# shutter.net
KiCad netlist of a schematic drawn in EAGLE
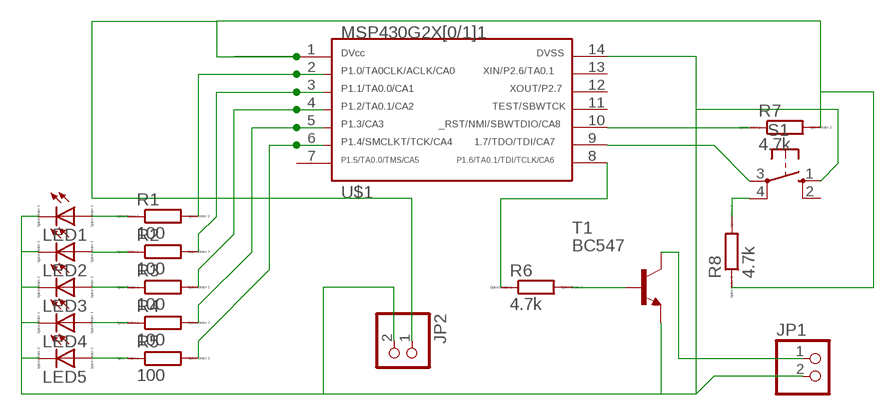
[diagram p0: schematic, sheet 1]

(export (version "E")
  (design (tool "Eeschema 10.0.6"))
  (components
    (comp (ref "JP1")
      (value "PINHD-1X2")
      (footprint "eagle-import:1X02")
      (libsource (lib "eagle-import") (part "PINHD-1X2"))
    )
    (comp (ref "JP2")
      (value "PINHD-1X2")
      (footprint "eagle-import:1X02")
      (libsource (lib "eagle-import") (part "PINHD-1X2"))
    )
    (comp (ref "LED1")
      (value "LED_ESML0603")
      (footprint "eagle-import:LED_SML0603")
      (libsource (lib "eagle-import") (part "LED_ESML0603"))
    )
    (comp (ref "LED2")
      (value "LED_ESML0603")
      (footprint "eagle-import:LED_SML0603")
      (libsource (lib "eagle-import") (part "LED_ESML0603"))
    )
    (comp (ref "LED3")
      (value "LED_ESML0603")
      (footprint "eagle-import:LED_SML0603")
      (libsource (lib "eagle-import") (part "LED_ESML0603"))
    )
    (comp (ref "LED4")
      (value "LED_ESML0603")
      (footprint "eagle-import:LED_SML0603")
      (libsource (lib "eagle-import") (part "LED_ESML0603"))
    )
    (comp (ref "LED5")
      (value "LED_ESML0603")
      (footprint "eagle-import:LED_SML0603")
      (libsource (lib "eagle-import") (part "LED_ESML0603"))
    )
    (comp (ref "R1")
      (value "100")
      (footprint "eagle-import:R0603")
      (libsource (lib "eagle-import") (part "RR0603"))
    )
    (comp (ref "R2")
      (value "100")
      (footprint "eagle-import:R0603")
      (libsource (lib "eagle-import") (part "RR0603"))
    )
    (comp (ref "R3")
      (value "100")
      (footprint "eagle-import:R0603")
      (libsource (lib "eagle-import") (part "RR0603"))
    )
    (comp (ref "R4")
      (value "100")
      (footprint "eagle-import:R0603")
      (libsource (lib "eagle-import") (part "RR0603"))
    )
    (comp (ref "R5")
      (value "100")
      (footprint "eagle-import:R0603")
      (libsource (lib "eagle-import") (part "RR0603"))
    )
    (comp (ref "R6")
      (value "4.7k")
      (footprint "eagle-import:R0603")
      (libsource (lib "eagle-import") (part "RR0603"))
    )
    (comp (ref "R7")
      (value "4.7k")
      (footprint "eagle-import:R0603")
      (libsource (lib "eagle-import") (part "RR0603"))
    )
    (comp (ref "R8")
      (value "4.7k")
      (footprint "eagle-import:R0603")
      (libsource (lib "eagle-import") (part "RR0603"))
    )
    (comp (ref "S1")
      (value "10-XX")
      (footprint "eagle-import:B3F-10XX")
      (fields (field (name "MPN") "B3F-1000"))
      (libsource (lib "eagle-import") (part "10-XX"))
    )
    (comp (ref "T1")
      (value "BC547")
      (footprint "eagle-import:TO92")
      (libsource (lib "eagle-import") (part "BC547"))
    )
    (comp (ref "U$1")
      (value "G2X[0/1]1---PW14")
      (footprint "eagle-import:PW14")
      (libsource (lib "eagle-import") (part "G2X[0/1]1---PW14"))
    )
  )
  (nets
    (net (code "1") (name "Net-(JP2-Pad1)") (class "Default")
      (node (ref "JP2") (pin "1") (pinfunction "1_1") (pintype "passive"))
      (node (ref "R7") (pin "2") (pinfunction "2_2") (pintype "passive"))
      (node (ref "R8") (pin "1") (pinfunction "1_1") (pintype "passive"))
      (node (ref "U$1") (pin "1") (pinfunction "1_1") (pintype "bidirectional"))
    )
    (net (code "2") (name "Net-(LED1-PadA)") (class "Default")
      (node (ref "LED1") (pin "A") (pinfunction "A_A") (pintype "passive"))
      (node (ref "R1") (pin "1") (pinfunction "1_1") (pintype "passive"))
    )
    (net (code "3") (name "Net-(LED2-PadA)") (class "Default")
      (node (ref "LED2") (pin "A") (pinfunction "A_A") (pintype "passive"))
      (node (ref "R2") (pin "1") (pinfunction "1_1") (pintype "passive"))
    )
    (net (code "4") (name "Net-(LED3-PadA)") (class "Default")
      (node (ref "LED3") (pin "A") (pinfunction "A_A") (pintype "passive"))
      (node (ref "R3") (pin "1") (pinfunction "1_1") (pintype "passive"))
    )
    (net (code "5") (name "Net-(LED4-PadA)") (class "Default")
      (node (ref "LED4") (pin "A") (pinfunction "A_A") (pintype "passive"))
      (node (ref "R4") (pin "1") (pinfunction "1_1") (pintype "passive"))
    )
    (net (code "6") (name "Net-(LED5-PadA)") (class "Default")
      (node (ref "LED5") (pin "A") (pinfunction "A_A") (pintype "passive"))
      (node (ref "R5") (pin "1") (pinfunction "1_1") (pintype "passive"))
    )
    (net (code "7") (name "Net-(R1-Pad2)") (class "Default")
      (node (ref "R1") (pin "2") (pinfunction "2_2") (pintype "passive"))
      (node (ref "U$1") (pin "2") (pinfunction "2_2") (pintype "bidirectional"))
    )
    (net (code "8") (name "Net-(R2-Pad2)") (class "Default")
      (node (ref "R2") (pin "2") (pinfunction "2_2") (pintype "passive"))
      (node (ref "U$1") (pin "3") (pinfunction "3_3") (pintype "bidirectional"))
    )
    (net (code "9") (name "Net-(R3-Pad2)") (class "Default")
      (node (ref "R3") (pin "2") (pinfunction "2_2") (pintype "passive"))
      (node (ref "U$1") (pin "4") (pinfunction "4_4") (pintype "bidirectional"))
    )
    (net (code "10") (name "Net-(R4-Pad2)") (class "Default")
      (node (ref "R4") (pin "2") (pinfunction "2_2") (pintype "passive"))
      (node (ref "U$1") (pin "5") (pinfunction "5_5") (pintype "bidirectional"))
    )
    (net (code "11") (name "Net-(R5-Pad2)") (class "Default")
      (node (ref "R5") (pin "2") (pinfunction "2_2") (pintype "passive"))
      (node (ref "U$1") (pin "6") (pinfunction "6_6") (pintype "bidirectional"))
    )
    (net (code "12") (name "Net-(R6-Pad1)") (class "Default")
      (node (ref "R6") (pin "1") (pinfunction "1_1") (pintype "passive"))
      (node (ref "U$1") (pin "8") (pinfunction "8_8") (pintype "bidirectional"))
    )
    (net (code "13") (name "Net-(R7-Pad1)") (class "Default")
      (node (ref "R7") (pin "1") (pinfunction "1_1") (pintype "passive"))
      (node (ref "U$1") (pin "10") (pinfunction "10_10") (pintype "bidirectional"))
    )
    (net (code "14") (name "Net-(S1-P)") (class "Default")
      (node (ref "S1") (pin "3") (pinfunction "P_3") (pintype "passive"))
      (node (ref "U$1") (pin "9") (pinfunction "9_9") (pintype "bidirectional"))
    )
    (net (code "15") (name "Net-(S1-P1)") (class "Default")
      (node (ref "R8") (pin "2") (pinfunction "2_2") (pintype "passive"))
      (node (ref "S1") (pin "4") (pinfunction "P1_4") (pintype "passive"))
    )
    (net (code "16") (name "Net-(S1-S)") (class "Default")
      (node (ref "JP1") (pin "2") (pinfunction "2_2") (pintype "passive"))
      (node (ref "JP2") (pin "2") (pinfunction "2_2") (pintype "passive"))
      (node (ref "LED1") (pin "C") (pinfunction "C_C") (pintype "passive"))
      (node (ref "LED2") (pin "C") (pinfunction "C_C") (pintype "passive"))
      (node (ref "LED3") (pin "C") (pinfunction "C_C") (pintype "passive"))
      (node (ref "LED4") (pin "C") (pinfunction "C_C") (pintype "passive"))
      (node (ref "LED5") (pin "C") (pinfunction "C_C") (pintype "passive"))
      (node (ref "S1") (pin "1") (pinfunction "S_1") (pintype "passive"))
      (node (ref "T1") (pin "1") (pinfunction "E_1") (pintype "passive"))
      (node (ref "U$1") (pin "14") (pinfunction "14_14") (pintype "bidirectional"))
    )
    (net (code "17") (name "Net-(T1-B)") (class "Default")
      (node (ref "R6") (pin "2") (pinfunction "2_2") (pintype "passive"))
      (node (ref "T1") (pin "2") (pinfunction "B_2") (pintype "passive"))
    )
    (net (code "18") (name "Net-(T1-C)") (class "Default")
      (node (ref "JP1") (pin "1") (pinfunction "1_1") (pintype "passive"))
      (node (ref "T1") (pin "3") (pinfunction "C_3") (pintype "passive"))
    )
    (net (code "19") (name "unconnected-(S1-S1-Pad2)") (class "Default")
      (node (ref "S1") (pin "2") (pinfunction "S1_2") (pintype "passive"))
    )
    (net (code "20") (name "unconnected-(U$1-Pad7)") (class "Default")
      (node (ref "U$1") (pin "7") (pinfunction "7_7") (pintype "bidirectional"))
    )
    (net (code "21") (name "unconnected-(U$1-Pad11)") (class "Default")
      (node (ref "U$1") (pin "11") (pinfunction "11_11") (pintype "bidirectional"))
    )
    (net (code "22") (name "unconnected-(U$1-Pad12)") (class "Default")
      (node (ref "U$1") (pin "12") (pinfunction "12_12") (pintype "bidirectional"))
    )
    (net (code "23") (name "unconnected-(U$1-Pad13)") (class "Default")
      (node (ref "U$1") (pin "13") (pinfunction "13_13") (pintype "bidirectional"))
    )
  )
)
